# DE-110817_02.net
KiCad netlist of a schematic drawn in Altium Designer
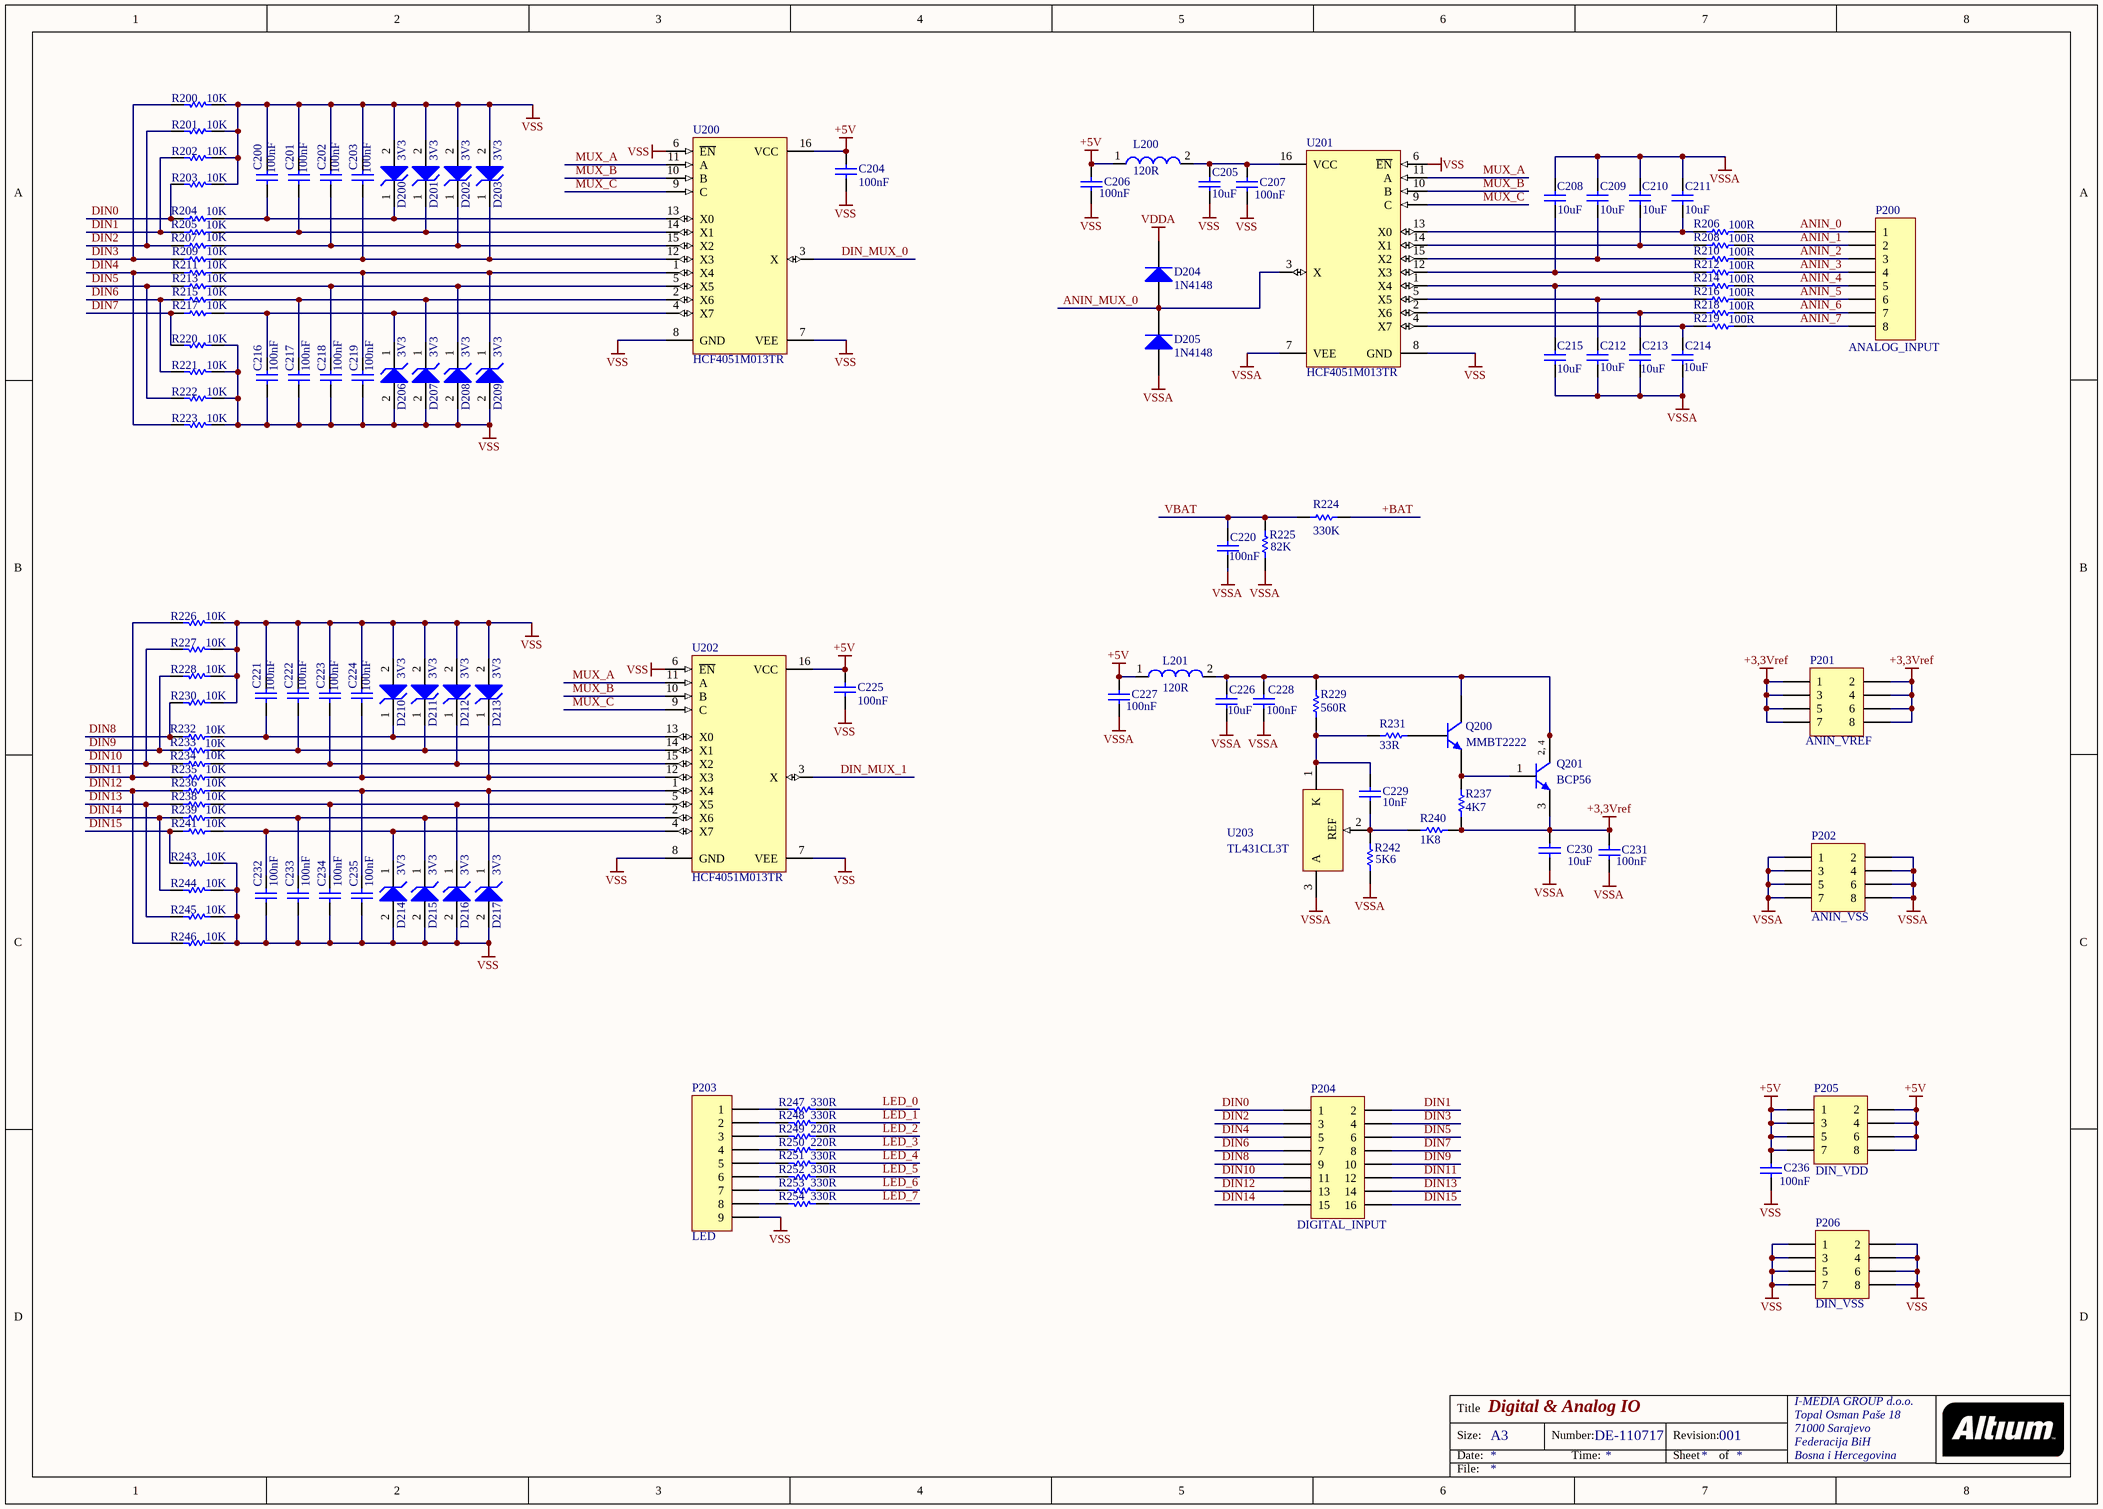
[diagram p0: DE-110817_02.SchDoc]

(export (version "E")
  (design (tool "Eeschema 10.0.6"))
  (components
    (comp (ref "C200")
      (value "100nF")
      (footprint "0603")
      (description "Ceramic Chip Capacitor - Standard")
      (libsource (lib "DE-251215") (part "C0603"))
    )
    (comp (ref "C201")
      (value "100nF")
      (footprint "0603")
      (description "Ceramic Chip Capacitor - Standard")
      (libsource (lib "DE-251215") (part "C0603"))
    )
    (comp (ref "C202")
      (value "100nF")
      (footprint "0603")
      (description "Ceramic Chip Capacitor - Standard")
      (libsource (lib "DE-251215") (part "C0603"))
    )
    (comp (ref "C203")
      (value "100nF")
      (footprint "0603")
      (description "Ceramic Chip Capacitor - Standard")
      (libsource (lib "DE-251215") (part "C0603"))
    )
    (comp (ref "C204")
      (value "100nF")
      (footprint "0603")
      (description "Ceramic Chip Capacitor - Standard")
      (libsource (lib "KEMET Chip Capacitor") (part "C0603"))
    )
    (comp (ref "C205")
      (value "10uF")
      (footprint "0805")
      (description "Ceramic Chip Capacitor - Standard")
      (libsource (lib "KEMET Chip Capacitor") (part "C0805"))
    )
    (comp (ref "C206")
      (value "100nF")
      (footprint "0603")
      (description "Ceramic Chip Capacitor - Standard")
      (libsource (lib "KEMET Chip Capacitor") (part "C0603"))
    )
    (comp (ref "C207")
      (value "100nF")
      (footprint "0603")
      (description "Ceramic Chip Capacitor - Standard")
      (libsource (lib "KEMET Chip Capacitor") (part "C0603"))
    )
    (comp (ref "C208")
      (value "10uF")
      (footprint "0805")
      (description "Ceramic Chip Capacitor - Standard")
      (libsource (lib "KEMET Chip Capacitor") (part "C0805"))
    )
    (comp (ref "C209")
      (value "10uF")
      (footprint "0805")
      (description "Ceramic Chip Capacitor - Standard")
      (libsource (lib "KEMET Chip Capacitor") (part "C0805"))
    )
    (comp (ref "C210")
      (value "10uF")
      (footprint "0805")
      (description "Ceramic Chip Capacitor - Standard")
      (libsource (lib "KEMET Chip Capacitor") (part "C0805"))
    )
    (comp (ref "C211")
      (value "10uF")
      (footprint "0805")
      (description "Ceramic Chip Capacitor - Standard")
      (libsource (lib "KEMET Chip Capacitor") (part "C0805"))
    )
    (comp (ref "C212")
      (value "10uF")
      (footprint "0805")
      (description "Ceramic Chip Capacitor - Standard")
      (libsource (lib "KEMET Chip Capacitor") (part "C0805"))
    )
    (comp (ref "C213")
      (value "10uF")
      (footprint "0805")
      (description "Ceramic Chip Capacitor - Standard")
      (libsource (lib "KEMET Chip Capacitor") (part "C0805"))
    )
    (comp (ref "C214")
      (value "10uF")
      (footprint "0805")
      (description "Ceramic Chip Capacitor - Standard")
      (libsource (lib "KEMET Chip Capacitor") (part "C0805"))
    )
    (comp (ref "C215")
      (value "10uF")
      (footprint "0805")
      (description "Ceramic Chip Capacitor - Standard")
      (libsource (lib "KEMET Chip Capacitor") (part "C0805"))
    )
    (comp (ref "C216")
      (value "100nF")
      (footprint "0603")
      (description "Ceramic Chip Capacitor - Standard")
      (libsource (lib "DE-251215") (part "C0603"))
    )
    (comp (ref "C217")
      (value "100nF")
      (footprint "0603")
      (description "Ceramic Chip Capacitor - Standard")
      (libsource (lib "DE-251215") (part "C0603"))
    )
    (comp (ref "C218")
      (value "100nF")
      (footprint "0603")
      (description "Ceramic Chip Capacitor - Standard")
      (libsource (lib "DE-251215") (part "C0603"))
    )
    (comp (ref "C219")
      (value "100nF")
      (footprint "0603")
      (description "Ceramic Chip Capacitor - Standard")
      (libsource (lib "DE-251215") (part "C0603"))
    )
    (comp (ref "C220")
      (value "100nF")
      (footprint "0603")
      (description "Ceramic Chip Capacitor - Standard")
      (libsource (lib "DE-251215") (part "C0603"))
    )
    (comp (ref "C221")
      (value "100nF")
      (footprint "0603")
      (description "Ceramic Chip Capacitor - Standard")
      (libsource (lib "DE-251215") (part "C0603"))
    )
    (comp (ref "C222")
      (value "100nF")
      (footprint "0603")
      (description "Ceramic Chip Capacitor - Standard")
      (libsource (lib "DE-251215") (part "C0603"))
    )
    (comp (ref "C223")
      (value "100nF")
      (footprint "0603")
      (description "Ceramic Chip Capacitor - Standard")
      (libsource (lib "DE-251215") (part "C0603"))
    )
    (comp (ref "C224")
      (value "100nF")
      (footprint "0603")
      (description "Ceramic Chip Capacitor - Standard")
      (libsource (lib "DE-251215") (part "C0603"))
    )
    (comp (ref "C225")
      (value "100nF")
      (footprint "0603")
      (description "Ceramic Chip Capacitor - Standard")
      (libsource (lib "KEMET Chip Capacitor") (part "C0603"))
    )
    (comp (ref "C226")
      (value "10uF")
      (footprint "0805")
      (description "Ceramic Chip Capacitor - Standard")
      (libsource (lib "KEMET Chip Capacitor") (part "C0805"))
    )
    (comp (ref "C227")
      (value "100nF")
      (footprint "0603")
      (description "Ceramic Chip Capacitor - Standard")
      (libsource (lib "KEMET Chip Capacitor") (part "C0603"))
    )
    (comp (ref "C228")
      (value "100nF")
      (footprint "0603")
      (description "Ceramic Chip Capacitor - Standard")
      (libsource (lib "KEMET Chip Capacitor") (part "C0603"))
    )
    (comp (ref "C229")
      (value "10nF")
      (footprint "0603")
      (description "Ceramic Chip Capacitor - Standard")
      (libsource (lib "KEMET Chip Capacitor") (part "C0603"))
    )
    (comp (ref "C230")
      (value "10uF")
      (footprint "0805")
      (description "Ceramic Chip Capacitor - Standard")
      (libsource (lib "KEMET Chip Capacitor") (part "C0805"))
    )
    (comp (ref "C231")
      (value "100nF")
      (footprint "0603")
      (description "Ceramic Chip Capacitor - Standard")
      (libsource (lib "KEMET Chip Capacitor") (part "C0603"))
    )
    (comp (ref "C232")
      (value "100nF")
      (footprint "0603")
      (description "Ceramic Chip Capacitor - Standard")
      (libsource (lib "DE-251215") (part "C0603"))
    )
    (comp (ref "C233")
      (value "100nF")
      (footprint "0603")
      (description "Ceramic Chip Capacitor - Standard")
      (libsource (lib "DE-251215") (part "C0603"))
    )
    (comp (ref "C234")
      (value "100nF")
      (footprint "0603")
      (description "Ceramic Chip Capacitor - Standard")
      (libsource (lib "DE-251215") (part "C0603"))
    )
    (comp (ref "C235")
      (value "100nF")
      (footprint "0603")
      (description "Ceramic Chip Capacitor - Standard")
      (libsource (lib "DE-251215") (part "C0603"))
    )
    (comp (ref "C236")
      (value "100nF")
      (footprint "0603")
      (description "Ceramic Chip Capacitor - Standard")
      (libsource (lib "KEMET Chip Capacitor") (part "C0603"))
    )
    (comp (ref "D200")
      (value "3V3")
      (footprint "ONSC-SOD-323-2-477-02_V")
      (description "Zener Voltage Regulator, 300 mW, 2-Pin SOD-323, Pb-Free, Tape and Reel")
      (fields (field (name "MANUFACTURER") "On Semiconductor") (field (name "PARTNUMBER") "MM3Z33VT1G"))
      (libsource (lib "ON Semi Zener Diodes") (part "MM3Z33VT1G"))
    )
    (comp (ref "D201")
      (value "3V3")
      (footprint "ONSC-SOD-323-2-477-02_V")
      (description "Zener Voltage Regulator, 300 mW, 2-Pin SOD-323, Pb-Free, Tape and Reel")
      (fields (field (name "MANUFACTURER") "On Semiconductor") (field (name "PARTNUMBER") "MM3Z33VT1G"))
      (libsource (lib "ON Semi Zener Diodes") (part "MM3Z33VT1G"))
    )
    (comp (ref "D202")
      (value "3V3")
      (footprint "ONSC-SOD-323-2-477-02_V")
      (description "Zener Voltage Regulator, 300 mW, 2-Pin SOD-323, Pb-Free, Tape and Reel")
      (fields (field (name "MANUFACTURER") "On Semiconductor") (field (name "PARTNUMBER") "MM3Z33VT1G"))
      (libsource (lib "ON Semi Zener Diodes") (part "MM3Z33VT1G"))
    )
    (comp (ref "D203")
      (value "3V3")
      (footprint "ONSC-SOD-323-2-477-02_V")
      (description "Zener Voltage Regulator, 300 mW, 2-Pin SOD-323, Pb-Free, Tape and Reel")
      (fields (field (name "MANUFACTURER") "On Semiconductor") (field (name "PARTNUMBER") "MM3Z33VT1G"))
      (libsource (lib "ON Semi Zener Diodes") (part "MM3Z33VT1G"))
    )
    (comp (ref "D204")
      (value "1N4148")
      (footprint "SOD323")
      (description "General-purpose Diode")
      (libsource (lib "Philips Discrete Diode - Switching") (part "BAS321"))
    )
    (comp (ref "D205")
      (value "1N4148")
      (footprint "SOD323")
      (description "General-purpose Diode")
      (libsource (lib "Philips Discrete Diode - Switching") (part "BAS321"))
    )
    (comp (ref "D206")
      (value "3V3")
      (footprint "ONSC-SOD-323-2-477-02_V")
      (description "Zener Voltage Regulator, 300 mW, 2-Pin SOD-323, Pb-Free, Tape and Reel")
      (fields (field (name "MANUFACTURER") "On Semiconductor") (field (name "PARTNUMBER") "MM3Z33VT1G"))
      (libsource (lib "ON Semi Zener Diodes") (part "MM3Z33VT1G"))
    )
    (comp (ref "D207")
      (value "3V3")
      (footprint "ONSC-SOD-323-2-477-02_V")
      (description "Zener Voltage Regulator, 300 mW, 2-Pin SOD-323, Pb-Free, Tape and Reel")
      (fields (field (name "MANUFACTURER") "On Semiconductor") (field (name "PARTNUMBER") "MM3Z33VT1G"))
      (libsource (lib "ON Semi Zener Diodes") (part "MM3Z33VT1G"))
    )
    (comp (ref "D208")
      (value "3V3")
      (footprint "ONSC-SOD-323-2-477-02_V")
      (description "Zener Voltage Regulator, 300 mW, 2-Pin SOD-323, Pb-Free, Tape and Reel")
      (fields (field (name "MANUFACTURER") "On Semiconductor") (field (name "PARTNUMBER") "MM3Z33VT1G"))
      (libsource (lib "ON Semi Zener Diodes") (part "MM3Z33VT1G"))
    )
    (comp (ref "D209")
      (value "3V3")
      (footprint "ONSC-SOD-323-2-477-02_V")
      (description "Zener Voltage Regulator, 300 mW, 2-Pin SOD-323, Pb-Free, Tape and Reel")
      (fields (field (name "MANUFACTURER") "On Semiconductor") (field (name "PARTNUMBER") "MM3Z33VT1G"))
      (libsource (lib "ON Semi Zener Diodes") (part "MM3Z33VT1G"))
    )
    (comp (ref "D210")
      (value "3V3")
      (footprint "ONSC-SOD-323-2-477-02_V")
      (description "Zener Voltage Regulator, 300 mW, 2-Pin SOD-323, Pb-Free, Tape and Reel")
      (fields (field (name "MANUFACTURER") "On Semiconductor") (field (name "PARTNUMBER") "MM3Z33VT1G"))
      (libsource (lib "ON Semi Zener Diodes") (part "MM3Z33VT1G"))
    )
    (comp (ref "D211")
      (value "3V3")
      (footprint "ONSC-SOD-323-2-477-02_V")
      (description "Zener Voltage Regulator, 300 mW, 2-Pin SOD-323, Pb-Free, Tape and Reel")
      (fields (field (name "MANUFACTURER") "On Semiconductor") (field (name "PARTNUMBER") "MM3Z33VT1G"))
      (libsource (lib "ON Semi Zener Diodes") (part "MM3Z33VT1G"))
    )
    (comp (ref "D212")
      (value "3V3")
      (footprint "ONSC-SOD-323-2-477-02_V")
      (description "Zener Voltage Regulator, 300 mW, 2-Pin SOD-323, Pb-Free, Tape and Reel")
      (fields (field (name "MANUFACTURER") "On Semiconductor") (field (name "PARTNUMBER") "MM3Z33VT1G"))
      (libsource (lib "ON Semi Zener Diodes") (part "MM3Z33VT1G"))
    )
    (comp (ref "D213")
      (value "3V3")
      (footprint "ONSC-SOD-323-2-477-02_V")
      (description "Zener Voltage Regulator, 300 mW, 2-Pin SOD-323, Pb-Free, Tape and Reel")
      (fields (field (name "MANUFACTURER") "On Semiconductor") (field (name "PARTNUMBER") "MM3Z33VT1G"))
      (libsource (lib "ON Semi Zener Diodes") (part "MM3Z33VT1G"))
    )
    (comp (ref "D214")
      (value "3V3")
      (footprint "ONSC-SOD-323-2-477-02_V")
      (description "Zener Voltage Regulator, 300 mW, 2-Pin SOD-323, Pb-Free, Tape and Reel")
      (fields (field (name "MANUFACTURER") "On Semiconductor") (field (name "PARTNUMBER") "MM3Z33VT1G"))
      (libsource (lib "ON Semi Zener Diodes") (part "MM3Z33VT1G"))
    )
    (comp (ref "D215")
      (value "3V3")
      (footprint "ONSC-SOD-323-2-477-02_V")
      (description "Zener Voltage Regulator, 300 mW, 2-Pin SOD-323, Pb-Free, Tape and Reel")
      (fields (field (name "MANUFACTURER") "On Semiconductor") (field (name "PARTNUMBER") "MM3Z33VT1G"))
      (libsource (lib "ON Semi Zener Diodes") (part "MM3Z33VT1G"))
    )
    (comp (ref "D216")
      (value "3V3")
      (footprint "ONSC-SOD-323-2-477-02_V")
      (description "Zener Voltage Regulator, 300 mW, 2-Pin SOD-323, Pb-Free, Tape and Reel")
      (fields (field (name "MANUFACTURER") "On Semiconductor") (field (name "PARTNUMBER") "MM3Z33VT1G"))
      (libsource (lib "ON Semi Zener Diodes") (part "MM3Z33VT1G"))
    )
    (comp (ref "D217")
      (value "3V3")
      (footprint "ONSC-SOD-323-2-477-02_V")
      (description "Zener Voltage Regulator, 300 mW, 2-Pin SOD-323, Pb-Free, Tape and Reel")
      (fields (field (name "MANUFACTURER") "On Semiconductor") (field (name "PARTNUMBER") "MM3Z33VT1G"))
      (libsource (lib "ON Semi Zener Diodes") (part "MM3Z33VT1G"))
    )
    (comp (ref "L200")
      (value "120R")
      (footprint "SMD-0805")
      (description "SMD EMI Suppression Ferrite Bead WE-CBF, Z = 120 Ohm")
      (fields (field (name "PARTNUMBER") "74279202"))
      (libsource (lib "WE-CBF SMD EMI Suppression Ferrite Bead") (part "74279202"))
    )
    (comp (ref "L201")
      (value "120R")
      (footprint "SMD-0805")
      (description "SMD EMI Suppression Ferrite Bead WE-CBF, Z = 120 Ohm")
      (fields (field (name "PARTNUMBER") "74279202"))
      (libsource (lib "WE-CBF SMD EMI Suppression Ferrite Bead") (part "74279202"))
    )
    (comp (ref "P200")
      (value "ANALOG_INPUT")
      (footprint "HDR1X8")
      (description "Header, 8-Pin")
      (libsource (lib "Miscellaneous Connectors") (part "Header 8"))
    )
    (comp (ref "P201")
      (value "ANIN_VREF")
      (footprint "HDR2X4")
      (description "Header, 4-Pin, Dual row")
      (libsource (lib "Miscellaneous Connectors") (part "Header 4X2"))
    )
    (comp (ref "P202")
      (value "ANIN_VSS")
      (footprint "HDR2X4")
      (description "Header, 4-Pin, Dual row")
      (libsource (lib "Miscellaneous Connectors") (part "Header 4X2"))
    )
    (comp (ref "P203")
      (value "LED")
      (footprint "HDR1X9")
      (description "Header, 9-Pin")
      (libsource (lib "Miscellaneous Connectors") (part "Header 9"))
    )
    (comp (ref "P204")
      (value "DIGITAL_INPUT")
      (footprint "HDR2X8")
      (description "Header, 8-Pin, Dual row")
      (libsource (lib "Miscellaneous Connectors") (part "Header 8X2"))
    )
    (comp (ref "P205")
      (value "DIN_VDD")
      (footprint "HDR2X4")
      (description "Header, 4-Pin, Dual row")
      (libsource (lib "Miscellaneous Connectors") (part "Header 4X2"))
    )
    (comp (ref "P206")
      (value "DIN_VSS")
      (footprint "HDR2X4")
      (description "Header, 4-Pin, Dual row")
      (libsource (lib "Miscellaneous Connectors") (part "Header 4X2"))
    )
    (comp (ref "Q200")
      (value "MMBT2222")
      (footprint "318-08")
      (description "General Purpose Transistor NPN Silicon")
      (libsource (lib "Motorola Discrete BJT") (part "MMBT2222ALT1"))
    )
    (comp (ref "Q201")
      (value "BCP56")
      (footprint "SOT223_N")
      (description "NPN Medium Power Transistor")
      (libsource (lib "Philips Discrete BJT - Medium Power") (part "BCP56"))
    )
    (comp (ref "R200") (value "10K") (footprint "ERA-0603") (libsource (lib "DE-200216_03") (part "ERAV")))
    (comp (ref "R201") (value "10K") (footprint "ERA-0603") (libsource (lib "DE-200216_03") (part "ERAV")))
    (comp (ref "R202") (value "10K") (footprint "ERA-0603") (libsource (lib "DE-200216_03") (part "ERAV")))
    (comp (ref "R203") (value "10K") (footprint "ERA-0603") (libsource (lib "DE-200216_03") (part "ERAV")))
    (comp (ref "R204") (value "10K") (footprint "ERA-0603") (libsource (lib "DE-200216_03") (part "ERAV")))
    (comp (ref "R205") (value "10K") (footprint "ERA-0603") (libsource (lib "DE-200216_03") (part "ERAV")))
    (comp (ref "R206") (value "100R") (footprint "ERA-0603") (libsource (lib "DE-200216_03") (part "ERAV")))
    (comp (ref "R207") (value "10K") (footprint "ERA-0603") (libsource (lib "DE-200216_03") (part "ERAV")))
    (comp (ref "R208") (value "100R") (footprint "ERA-0603") (libsource (lib "DE-200216_03") (part "ERAV")))
    (comp (ref "R209") (value "10K") (footprint "ERA-0603") (libsource (lib "DE-251215") (part "ERAV")))
    (comp (ref "R210") (value "100R") (footprint "ERA-0603") (libsource (lib "DE-200216_03") (part "ERAV")))
    (comp (ref "R211") (value "10K") (footprint "ERA-0603") (libsource (lib "DE-251215") (part "ERAV")))
    (comp (ref "R212") (value "100R") (footprint "ERA-0603") (libsource (lib "DE-200216_03") (part "ERAV")))
    (comp (ref "R213") (value "10K") (footprint "ERA-0603") (libsource (lib "DE-251215") (part "ERAV")))
    (comp (ref "R214") (value "100R") (footprint "ERA-0603") (libsource (lib "DE-200216_03") (part "ERAV")))
    (comp (ref "R215") (value "10K") (footprint "ERA-0603") (libsource (lib "DE-251215") (part "ERAV")))
    (comp (ref "R216") (value "100R") (footprint "ERA-0603") (libsource (lib "DE-200216_03") (part "ERAV")))
    (comp (ref "R217") (value "10K") (footprint "ERA-0603") (libsource (lib "DE-251215") (part "ERAV")))
    (comp (ref "R218") (value "100R") (footprint "ERA-0603") (libsource (lib "DE-200216_03") (part "ERAV")))
    (comp (ref "R219") (value "100R") (footprint "ERA-0603") (libsource (lib "DE-200216_03") (part "ERAV")))
    (comp (ref "R220") (value "10K") (footprint "ERA-0603") (libsource (lib "DE-200216_03") (part "ERAV")))
    (comp (ref "R221") (value "10K") (footprint "ERA-0603") (libsource (lib "DE-200216_03") (part "ERAV")))
    (comp (ref "R222") (value "10K") (footprint "ERA-0603") (libsource (lib "DE-200216_03") (part "ERAV")))
    (comp (ref "R223") (value "10K") (footprint "ERA-0603") (libsource (lib "DE-200216_03") (part "ERAV")))
    (comp (ref "R224") (value "330K") (footprint "ERA-0603") (libsource (lib "DE-200216_03") (part "ERAV")))
    (comp (ref "R225") (value "82K") (footprint "ERA-0603") (libsource (lib "DE-200216_03") (part "ERAV")))
    (comp (ref "R226") (value "10K") (footprint "ERA-0603") (libsource (lib "DE-200216_03") (part "ERAV")))
    (comp (ref "R227") (value "10K") (footprint "ERA-0603") (libsource (lib "DE-200216_03") (part "ERAV")))
    (comp (ref "R228") (value "10K") (footprint "ERA-0603") (libsource (lib "DE-200216_03") (part "ERAV")))
    (comp (ref "R229") (value "560R") (footprint "ERA-0603") (libsource (lib "DE-200216_03") (part "ERAV")))
    (comp (ref "R230") (value "10K") (footprint "ERA-0603") (libsource (lib "DE-200216_03") (part "ERAV")))
    (comp (ref "R231") (value "33R") (footprint "ERA-0603") (libsource (lib "DE-200216_03") (part "ERAV")))
    (comp (ref "R232") (value "10K") (footprint "ERA-0603") (libsource (lib "DE-200216_03") (part "ERAV")))
    (comp (ref "R233") (value "10K") (footprint "ERA-0603") (libsource (lib "DE-200216_03") (part "ERAV")))
    (comp (ref "R234") (value "10K") (footprint "ERA-0603") (libsource (lib "DE-200216_03") (part "ERAV")))
    (comp (ref "R235") (value "10K") (footprint "ERA-0603") (libsource (lib "DE-251215") (part "ERAV")))
    (comp (ref "R236") (value "10K") (footprint "ERA-0603") (libsource (lib "DE-251215") (part "ERAV")))
    (comp (ref "R237") (value "4K7") (footprint "ERA-0603") (libsource (lib "DE-200216_03") (part "ERAV")))
    (comp (ref "R238") (value "10K") (footprint "ERA-0603") (libsource (lib "DE-251215") (part "ERAV")))
    (comp (ref "R239") (value "10K") (footprint "ERA-0603") (libsource (lib "DE-251215") (part "ERAV")))
    (comp (ref "R240") (value "1K8") (footprint "ERA-0603") (libsource (lib "DE-200216_03") (part "ERAV")))
    (comp (ref "R241") (value "10K") (footprint "ERA-0603") (libsource (lib "DE-251215") (part "ERAV")))
    (comp (ref "R242") (value "5K6") (footprint "ERA-0603") (libsource (lib "DE-200216_03") (part "ERAV")))
    (comp (ref "R243") (value "10K") (footprint "ERA-0603") (libsource (lib "DE-200216_03") (part "ERAV")))
    (comp (ref "R244") (value "10K") (footprint "ERA-0603") (libsource (lib "DE-200216_03") (part "ERAV")))
    (comp (ref "R245") (value "10K") (footprint "ERA-0603") (libsource (lib "DE-200216_03") (part "ERAV")))
    (comp (ref "R246") (value "10K") (footprint "ERA-0603") (libsource (lib "DE-200216_03") (part "ERAV")))
    (comp (ref "R247") (value "330R") (footprint "ERA-0603") (libsource (lib "DE-200216_03") (part "ERAV")))
    (comp (ref "R248") (value "330R") (footprint "ERA-0603") (libsource (lib "DE-200216_03") (part "ERAV")))
    (comp (ref "R249") (value "220R") (footprint "ERA-0603") (libsource (lib "DE-200216_03") (part "ERAV")))
    (comp (ref "R250") (value "220R") (footprint "ERA-0603") (libsource (lib "DE-200216_03") (part "ERAV")))
    (comp (ref "R251") (value "330R") (footprint "ERA-0603") (libsource (lib "DE-200216_03") (part "ERAV")))
    (comp (ref "R252") (value "330R") (footprint "ERA-0603") (libsource (lib "DE-200216_03") (part "ERAV")))
    (comp (ref "R253") (value "330R") (footprint "ERA-0603") (libsource (lib "DE-200216_03") (part "ERAV")))
    (comp (ref "R254") (value "330R") (footprint "ERA-0603") (libsource (lib "DE-200216_03") (part "ERAV")))
    (comp (ref "U200")
      (value "HCF4051M013TR")
      (footprint "M16A_N")
      (description "8-Channel Analog Multiplexer/Demultiplexer")
      (libsource (lib "DE-110817") (part "CD4051BCM"))
    )
    (comp (ref "U201")
      (value "HCF4051M013TR")
      (footprint "M16A_N")
      (description "8-Channel Analog Multiplexer/Demultiplexer")
      (libsource (lib "") (part "CD4051BCM_1"))
    )
    (comp (ref "U202")
      (value "HCF4051M013TR")
      (footprint "M16A_N")
      (description "8-Channel Analog Multiplexer/Demultiplexer")
      (libsource (lib "DE-110817") (part "CD4051BCM"))
    )
    (comp (ref "U203")
      (value "TL431CL3T")
      (footprint "SOT23-3_N")
      (description "Programmable Voltage Reference, 2.5 to 36V, 3-Pin SOT23-3, Tape and Reel")
      (libsource (lib "STMicroelectronics Power Management Voltage Reference") (part "TL431CL3T"))
    )
  )
  (nets
    (net (code "1") (name "+3,3Vref") (class "Default")
      (node (ref "C230") (pin "2") (pinfunction "2_2") (pintype "passive"))
      (node (ref "C231") (pin "2") (pinfunction "2_2") (pintype "passive"))
      (node (ref "P201") (pin "1") (pinfunction "1_1") (pintype "passive"))
      (node (ref "P201") (pin "2") (pinfunction "2_2") (pintype "passive"))
      (node (ref "P201") (pin "3") (pinfunction "3_3") (pintype "passive"))
      (node (ref "P201") (pin "4") (pinfunction "4_4") (pintype "passive"))
      (node (ref "P201") (pin "5") (pinfunction "5_5") (pintype "passive"))
      (node (ref "P201") (pin "6") (pinfunction "6_6") (pintype "passive"))
      (node (ref "P201") (pin "7") (pinfunction "7_7") (pintype "passive"))
      (node (ref "P201") (pin "8") (pinfunction "8_8") (pintype "passive"))
      (node (ref "Q201") (pin "3") (pinfunction "E_3") (pintype "passive"))
      (node (ref "R237") (pin "2") (pinfunction "2_2") (pintype "passive"))
      (node (ref "R240") (pin "2") (pinfunction "2_2") (pintype "passive"))
    )
    (net (code "2") (name "+5V") (class "Default")
      (node (ref "C204") (pin "2") (pinfunction "2_2") (pintype "passive"))
      (node (ref "C206") (pin "2") (pinfunction "2_2") (pintype "passive"))
      (node (ref "C225") (pin "2") (pinfunction "2_2") (pintype "passive"))
      (node (ref "C227") (pin "2") (pinfunction "2_2") (pintype "passive"))
      (node (ref "C236") (pin "2") (pinfunction "2_2") (pintype "passive"))
      (node (ref "L200") (pin "1") (pinfunction "1_1") (pintype "passive"))
      (node (ref "L201") (pin "1") (pinfunction "1_1") (pintype "passive"))
      (node (ref "P205") (pin "1") (pinfunction "1_1") (pintype "passive"))
      (node (ref "P205") (pin "2") (pinfunction "2_2") (pintype "passive"))
      (node (ref "P205") (pin "3") (pinfunction "3_3") (pintype "passive"))
      (node (ref "P205") (pin "4") (pinfunction "4_4") (pintype "passive"))
      (node (ref "P205") (pin "5") (pinfunction "5_5") (pintype "passive"))
      (node (ref "P205") (pin "6") (pinfunction "6_6") (pintype "passive"))
      (node (ref "P205") (pin "7") (pinfunction "7_7") (pintype "passive"))
      (node (ref "P205") (pin "8") (pinfunction "8_8") (pintype "passive"))
      (node (ref "U200") (pin "16") (pinfunction "VCC_16") (pintype "power_in"))
      (node (ref "U202") (pin "16") (pinfunction "VCC_16") (pintype "power_in"))
    )
    (net (code "3") (name "/+BAT") (class "Default")
      (node (ref "R224") (pin "2") (pinfunction "2_2") (pintype "passive"))
    )
    (net (code "4") (name "/ANIN_0") (class "Default")
      (node (ref "P200") (pin "1") (pinfunction "1_1") (pintype "passive"))
      (node (ref "R206") (pin "2") (pinfunction "2_2") (pintype "passive"))
    )
    (net (code "5") (name "/ANIN_1") (class "Default")
      (node (ref "P200") (pin "2") (pinfunction "2_2") (pintype "passive"))
      (node (ref "R208") (pin "2") (pinfunction "2_2") (pintype "passive"))
    )
    (net (code "6") (name "/ANIN_2") (class "Default")
      (node (ref "P200") (pin "3") (pinfunction "3_3") (pintype "passive"))
      (node (ref "R210") (pin "2") (pinfunction "2_2") (pintype "passive"))
    )
    (net (code "7") (name "/ANIN_3") (class "Default")
      (node (ref "P200") (pin "4") (pinfunction "4_4") (pintype "passive"))
      (node (ref "R212") (pin "2") (pinfunction "2_2") (pintype "passive"))
    )
    (net (code "8") (name "/ANIN_4") (class "Default")
      (node (ref "P200") (pin "5") (pinfunction "5_5") (pintype "passive"))
      (node (ref "R214") (pin "2") (pinfunction "2_2") (pintype "passive"))
    )
    (net (code "9") (name "/ANIN_5") (class "Default")
      (node (ref "P200") (pin "6") (pinfunction "6_6") (pintype "passive"))
      (node (ref "R216") (pin "2") (pinfunction "2_2") (pintype "passive"))
    )
    (net (code "10") (name "/ANIN_6") (class "Default")
      (node (ref "P200") (pin "7") (pinfunction "7_7") (pintype "passive"))
      (node (ref "R218") (pin "2") (pinfunction "2_2") (pintype "passive"))
    )
    (net (code "11") (name "/ANIN_7") (class "Default")
      (node (ref "P200") (pin "8") (pinfunction "8_8") (pintype "passive"))
      (node (ref "R219") (pin "2") (pinfunction "2_2") (pintype "passive"))
    )
    (net (code "12") (name "/ANIN_MUX_0") (class "Default")
      (node (ref "D204") (pin "2") (pinfunction "A_2") (pintype "passive"))
      (node (ref "D205") (pin "1") (pinfunction "K_1") (pintype "passive"))
      (node (ref "U201") (pin "3") (pinfunction "X_3") (pintype "bidirectional"))
    )
    (net (code "13") (name "/DIN0") (class "Default")
      (node (ref "P204") (pin "1") (pinfunction "1_1") (pintype "passive"))
      (node (ref "R203") (pin "2") (pinfunction "2_2") (pintype "passive"))
      (node (ref "R204") (pin "1") (pinfunction "1_1") (pintype "passive"))
    )
    (net (code "14") (name "/DIN1") (class "Default")
      (node (ref "P204") (pin "2") (pinfunction "2_2") (pintype "passive"))
      (node (ref "R202") (pin "2") (pinfunction "2_2") (pintype "passive"))
      (node (ref "R205") (pin "1") (pinfunction "1_1") (pintype "passive"))
    )
    (net (code "15") (name "/DIN2") (class "Default")
      (node (ref "P204") (pin "3") (pinfunction "3_3") (pintype "passive"))
      (node (ref "R201") (pin "2") (pinfunction "2_2") (pintype "passive"))
      (node (ref "R207") (pin "1") (pinfunction "1_1") (pintype "passive"))
    )
    (net (code "16") (name "/DIN3") (class "Default")
      (node (ref "P204") (pin "4") (pinfunction "4_4") (pintype "passive"))
      (node (ref "R200") (pin "2") (pinfunction "2_2") (pintype "passive"))
      (node (ref "R209") (pin "1") (pinfunction "1_1") (pintype "passive"))
    )
    (net (code "17") (name "/DIN4") (class "Default")
      (node (ref "P204") (pin "5") (pinfunction "5_5") (pintype "passive"))
      (node (ref "R211") (pin "1") (pinfunction "1_1") (pintype "passive"))
      (node (ref "R223") (pin "2") (pinfunction "2_2") (pintype "passive"))
    )
    (net (code "18") (name "/DIN5") (class "Default")
      (node (ref "P204") (pin "6") (pinfunction "6_6") (pintype "passive"))
      (node (ref "R213") (pin "1") (pinfunction "1_1") (pintype "passive"))
      (node (ref "R222") (pin "2") (pinfunction "2_2") (pintype "passive"))
    )
    (net (code "19") (name "/DIN6") (class "Default")
      (node (ref "P204") (pin "7") (pinfunction "7_7") (pintype "passive"))
      (node (ref "R215") (pin "1") (pinfunction "1_1") (pintype "passive"))
      (node (ref "R221") (pin "2") (pinfunction "2_2") (pintype "passive"))
    )
    (net (code "20") (name "/DIN7") (class "Default")
      (node (ref "P204") (pin "8") (pinfunction "8_8") (pintype "passive"))
      (node (ref "R217") (pin "1") (pinfunction "1_1") (pintype "passive"))
      (node (ref "R220") (pin "2") (pinfunction "2_2") (pintype "passive"))
    )
    (net (code "21") (name "/DIN8") (class "Default")
      (node (ref "P204") (pin "9") (pinfunction "9_9") (pintype "passive"))
      (node (ref "R230") (pin "2") (pinfunction "2_2") (pintype "passive"))
      (node (ref "R232") (pin "1") (pinfunction "1_1") (pintype "passive"))
    )
    (net (code "22") (name "/DIN9") (class "Default")
      (node (ref "P204") (pin "10") (pinfunction "10_10") (pintype "passive"))
      (node (ref "R228") (pin "2") (pinfunction "2_2") (pintype "passive"))
      (node (ref "R233") (pin "1") (pinfunction "1_1") (pintype "passive"))
    )
    (net (code "23") (name "/DIN10") (class "Default")
      (node (ref "P204") (pin "11") (pinfunction "11_11") (pintype "passive"))
      (node (ref "R227") (pin "2") (pinfunction "2_2") (pintype "passive"))
      (node (ref "R234") (pin "1") (pinfunction "1_1") (pintype "passive"))
    )
    (net (code "24") (name "/DIN11") (class "Default")
      (node (ref "P204") (pin "12") (pinfunction "12_12") (pintype "passive"))
      (node (ref "R226") (pin "2") (pinfunction "2_2") (pintype "passive"))
      (node (ref "R235") (pin "1") (pinfunction "1_1") (pintype "passive"))
    )
    (net (code "25") (name "/DIN12") (class "Default")
      (node (ref "P204") (pin "13") (pinfunction "13_13") (pintype "passive"))
      (node (ref "R236") (pin "1") (pinfunction "1_1") (pintype "passive"))
      (node (ref "R246") (pin "2") (pinfunction "2_2") (pintype "passive"))
    )
    (net (code "26") (name "/DIN13") (class "Default")
      (node (ref "P204") (pin "14") (pinfunction "14_14") (pintype "passive"))
      (node (ref "R238") (pin "1") (pinfunction "1_1") (pintype "passive"))
      (node (ref "R245") (pin "2") (pinfunction "2_2") (pintype "passive"))
    )
    (net (code "27") (name "/DIN14") (class "Default")
      (node (ref "P204") (pin "15") (pinfunction "15_15") (pintype "passive"))
      (node (ref "R239") (pin "1") (pinfunction "1_1") (pintype "passive"))
      (node (ref "R244") (pin "2") (pinfunction "2_2") (pintype "passive"))
    )
    (net (code "28") (name "/DIN15") (class "Default")
      (node (ref "P204") (pin "16") (pinfunction "16_16") (pintype "passive"))
      (node (ref "R241") (pin "1") (pinfunction "1_1") (pintype "passive"))
      (node (ref "R243") (pin "2") (pinfunction "2_2") (pintype "passive"))
    )
    (net (code "29") (name "/DIN_MUX_0") (class "Default")
      (node (ref "U200") (pin "3") (pinfunction "X_3") (pintype "bidirectional"))
    )
    (net (code "30") (name "/DIN_MUX_1") (class "Default")
      (node (ref "U202") (pin "3") (pinfunction "X_3") (pintype "bidirectional"))
    )
    (net (code "31") (name "/LED_0") (class "Default")
      (node (ref "R247") (pin "2") (pinfunction "2_2") (pintype "passive"))
    )
    (net (code "32") (name "/LED_1") (class "Default")
      (node (ref "R248") (pin "2") (pinfunction "2_2") (pintype "passive"))
    )
    (net (code "33") (name "/LED_2") (class "Default")
      (node (ref "R249") (pin "2") (pinfunction "2_2") (pintype "passive"))
    )
    (net (code "34") (name "/LED_3") (class "Default")
      (node (ref "R250") (pin "2") (pinfunction "2_2") (pintype "passive"))
    )
    (net (code "35") (name "/LED_4") (class "Default")
      (node (ref "R251") (pin "2") (pinfunction "2_2") (pintype "passive"))
    )
    (net (code "36") (name "/LED_5") (class "Default")
      (node (ref "R252") (pin "2") (pinfunction "2_2") (pintype "passive"))
    )
    (net (code "37") (name "/LED_6") (class "Default")
      (node (ref "R253") (pin "2") (pinfunction "2_2") (pintype "passive"))
    )
    (net (code "38") (name "/LED_7") (class "Default")
      (node (ref "R254") (pin "2") (pinfunction "2_2") (pintype "passive"))
    )
    (net (code "39") (name "/MUX_A") (class "Default")
      (node (ref "U200") (pin "11") (pinfunction "A_11") (pintype "input"))
      (node (ref "U201") (pin "11") (pinfunction "A_11") (pintype "input"))
      (node (ref "U202") (pin "11") (pinfunction "A_11") (pintype "input"))
    )
    (net (code "40") (name "/MUX_B") (class "Default")
      (node (ref "U200") (pin "10") (pinfunction "B_10") (pintype "input"))
      (node (ref "U201") (pin "10") (pinfunction "B_10") (pintype "input"))
      (node (ref "U202") (pin "10") (pinfunction "B_10") (pintype "input"))
    )
    (net (code "41") (name "/MUX_C") (class "Default")
      (node (ref "U200") (pin "9") (pinfunction "C_9") (pintype "input"))
      (node (ref "U201") (pin "9") (pinfunction "C_9") (pintype "input"))
      (node (ref "U202") (pin "9") (pinfunction "C_9") (pintype "input"))
    )
    (net (code "42") (name "/VBAT") (class "Default")
      (node (ref "C220") (pin "2") (pinfunction "2_2") (pintype "passive"))
      (node (ref "R224") (pin "1") (pinfunction "1_1") (pintype "passive"))
      (node (ref "R225") (pin "2") (pinfunction "2_2") (pintype "passive"))
    )
    (net (code "43") (name "Net-(D200-K)") (class "Default")
      (node (ref "C200") (pin "2") (pinfunction "2_2") (pintype "passive"))
      (node (ref "D200") (pin "1") (pinfunction "K_1") (pintype "passive"))
      (node (ref "R204") (pin "2") (pinfunction "2_2") (pintype "passive"))
      (node (ref "U200") (pin "13") (pinfunction "X0_13") (pintype "bidirectional"))
    )
    (net (code "44") (name "Net-(D201-K)") (class "Default")
      (node (ref "C201") (pin "2") (pinfunction "2_2") (pintype "passive"))
      (node (ref "D201") (pin "1") (pinfunction "K_1") (pintype "passive"))
      (node (ref "R205") (pin "2") (pinfunction "2_2") (pintype "passive"))
      (node (ref "U200") (pin "14") (pinfunction "X1_14") (pintype "bidirectional"))
    )
    (net (code "45") (name "Net-(D202-K)") (class "Default")
      (node (ref "C202") (pin "2") (pinfunction "2_2") (pintype "passive"))
      (node (ref "D202") (pin "1") (pinfunction "K_1") (pintype "passive"))
      (node (ref "R207") (pin "2") (pinfunction "2_2") (pintype "passive"))
      (node (ref "U200") (pin "15") (pinfunction "X2_15") (pintype "bidirectional"))
    )
    (net (code "46") (name "Net-(D203-K)") (class "Default")
      (node (ref "C203") (pin "2") (pinfunction "2_2") (pintype "passive"))
      (node (ref "D203") (pin "1") (pinfunction "K_1") (pintype "passive"))
      (node (ref "R209") (pin "2") (pinfunction "2_2") (pintype "passive"))
      (node (ref "U200") (pin "12") (pinfunction "X3_12") (pintype "bidirectional"))
    )
    (net (code "47") (name "Net-(D206-K)") (class "Default")
      (node (ref "C216") (pin "2") (pinfunction "2_2") (pintype "passive"))
      (node (ref "D206") (pin "1") (pinfunction "K_1") (pintype "passive"))
      (node (ref "R217") (pin "2") (pinfunction "2_2") (pintype "passive"))
      (node (ref "U200") (pin "4") (pinfunction "X7_4") (pintype "bidirectional"))
    )
    (net (code "48") (name "Net-(D207-K)") (class "Default")
      (node (ref "C217") (pin "2") (pinfunction "2_2") (pintype "passive"))
      (node (ref "D207") (pin "1") (pinfunction "K_1") (pintype "passive"))
      (node (ref "R215") (pin "2") (pinfunction "2_2") (pintype "passive"))
      (node (ref "U200") (pin "2") (pinfunction "X6_2") (pintype "bidirectional"))
    )
    (net (code "49") (name "Net-(D208-K)") (class "Default")
      (node (ref "C218") (pin "2") (pinfunction "2_2") (pintype "passive"))
      (node (ref "D208") (pin "1") (pinfunction "K_1") (pintype "passive"))
      (node (ref "R213") (pin "2") (pinfunction "2_2") (pintype "passive"))
      (node (ref "U200") (pin "5") (pinfunction "X5_5") (pintype "bidirectional"))
    )
    (net (code "50") (name "Net-(D209-K)") (class "Default")
      (node (ref "C219") (pin "2") (pinfunction "2_2") (pintype "passive"))
      (node (ref "D209") (pin "1") (pinfunction "K_1") (pintype "passive"))
      (node (ref "R211") (pin "2") (pinfunction "2_2") (pintype "passive"))
      (node (ref "U200") (pin "1") (pinfunction "X4_1") (pintype "bidirectional"))
    )
    (net (code "51") (name "Net-(D210-K)") (class "Default")
      (node (ref "C221") (pin "2") (pinfunction "2_2") (pintype "passive"))
      (node (ref "D210") (pin "1") (pinfunction "K_1") (pintype "passive"))
      (node (ref "R232") (pin "2") (pinfunction "2_2") (pintype "passive"))
      (node (ref "U202") (pin "13") (pinfunction "X0_13") (pintype "bidirectional"))
    )
    (net (code "52") (name "Net-(D211-K)") (class "Default")
      (node (ref "C222") (pin "2") (pinfunction "2_2") (pintype "passive"))
      (node (ref "D211") (pin "1") (pinfunction "K_1") (pintype "passive"))
      (node (ref "R233") (pin "2") (pinfunction "2_2") (pintype "passive"))
      (node (ref "U202") (pin "14") (pinfunction "X1_14") (pintype "bidirectional"))
    )
    (net (code "53") (name "Net-(D212-K)") (class "Default")
      (node (ref "C223") (pin "2") (pinfunction "2_2") (pintype "passive"))
      (node (ref "D212") (pin "1") (pinfunction "K_1") (pintype "passive"))
      (node (ref "R234") (pin "2") (pinfunction "2_2") (pintype "passive"))
      (node (ref "U202") (pin "15") (pinfunction "X2_15") (pintype "bidirectional"))
    )
    (net (code "54") (name "Net-(D213-K)") (class "Default")
      (node (ref "C224") (pin "2") (pinfunction "2_2") (pintype "passive"))
      (node (ref "D213") (pin "1") (pinfunction "K_1") (pintype "passive"))
      (node (ref "R235") (pin "2") (pinfunction "2_2") (pintype "passive"))
      (node (ref "U202") (pin "12") (pinfunction "X3_12") (pintype "bidirectional"))
    )
    (net (code "55") (name "Net-(D214-K)") (class "Default")
      (node (ref "C232") (pin "2") (pinfunction "2_2") (pintype "passive"))
      (node (ref "D214") (pin "1") (pinfunction "K_1") (pintype "passive"))
      (node (ref "R241") (pin "2") (pinfunction "2_2") (pintype "passive"))
      (node (ref "U202") (pin "4") (pinfunction "X7_4") (pintype "bidirectional"))
    )
    (net (code "56") (name "Net-(D215-K)") (class "Default")
      (node (ref "C233") (pin "2") (pinfunction "2_2") (pintype "passive"))
      (node (ref "D215") (pin "1") (pinfunction "K_1") (pintype "passive"))
      (node (ref "R239") (pin "2") (pinfunction "2_2") (pintype "passive"))
      (node (ref "U202") (pin "2") (pinfunction "X6_2") (pintype "bidirectional"))
    )
    (net (code "57") (name "Net-(D216-K)") (class "Default")
      (node (ref "C234") (pin "2") (pinfunction "2_2") (pintype "passive"))
      (node (ref "D216") (pin "1") (pinfunction "K_1") (pintype "passive"))
      (node (ref "R238") (pin "2") (pinfunction "2_2") (pintype "passive"))
      (node (ref "U202") (pin "5") (pinfunction "X5_5") (pintype "bidirectional"))
    )
    (net (code "58") (name "Net-(D217-K)") (class "Default")
      (node (ref "C235") (pin "2") (pinfunction "2_2") (pintype "passive"))
      (node (ref "D217") (pin "1") (pinfunction "K_1") (pintype "passive"))
      (node (ref "R236") (pin "2") (pinfunction "2_2") (pintype "passive"))
      (node (ref "U202") (pin "1") (pinfunction "X4_1") (pintype "bidirectional"))
    )
    (net (code "59") (name "Net-(P203-Pad1)") (class "Default")
      (node (ref "P203") (pin "1") (pinfunction "1_1") (pintype "passive"))
      (node (ref "R247") (pin "1") (pinfunction "1_1") (pintype "passive"))
    )
    (net (code "60") (name "Net-(P203-Pad2)") (class "Default")
      (node (ref "P203") (pin "2") (pinfunction "2_2") (pintype "passive"))
      (node (ref "R248") (pin "1") (pinfunction "1_1") (pintype "passive"))
    )
    (net (code "61") (name "Net-(P203-Pad3)") (class "Default")
      (node (ref "P203") (pin "3") (pinfunction "3_3") (pintype "passive"))
      (node (ref "R249") (pin "1") (pinfunction "1_1") (pintype "passive"))
    )
    (net (code "62") (name "Net-(P203-Pad4)") (class "Default")
      (node (ref "P203") (pin "4") (pinfunction "4_4") (pintype "passive"))
      (node (ref "R250") (pin "1") (pinfunction "1_1") (pintype "passive"))
    )
    (net (code "63") (name "Net-(P203-Pad5)") (class "Default")
      (node (ref "P203") (pin "5") (pinfunction "5_5") (pintype "passive"))
      (node (ref "R251") (pin "1") (pinfunction "1_1") (pintype "passive"))
    )
    (net (code "64") (name "Net-(P203-Pad6)") (class "Default")
      (node (ref "P203") (pin "6") (pinfunction "6_6") (pintype "passive"))
      (node (ref "R252") (pin "1") (pinfunction "1_1") (pintype "passive"))
    )
    (net (code "65") (name "Net-(P203-Pad7)") (class "Default")
      (node (ref "P203") (pin "7") (pinfunction "7_7") (pintype "passive"))
      (node (ref "R253") (pin "1") (pinfunction "1_1") (pintype "passive"))
    )
    (net (code "66") (name "Net-(P203-Pad8)") (class "Default")
      (node (ref "P203") (pin "8") (pinfunction "8_8") (pintype "passive"))
      (node (ref "R254") (pin "1") (pinfunction "1_1") (pintype "passive"))
    )
    (net (code "67") (name "Net-(Q200-B)") (class "Default")
      (node (ref "Q200") (pin "1") (pinfunction "B_1") (pintype "passive"))
      (node (ref "R231") (pin "1") (pinfunction "1_1") (pintype "passive"))
    )
    (net (code "68") (name "Net-(Q200-C)") (class "Default")
      (node (ref "C226") (pin "2") (pinfunction "2_2") (pintype "passive"))
      (node (ref "C228") (pin "2") (pinfunction "2_2") (pintype "passive"))
      (node (ref "L201") (pin "2") (pinfunction "2_2") (pintype "passive"))
      (node (ref "Q200") (pin "3") (pinfunction "C_3") (pintype "passive"))
      (node (ref "Q201") (pin "2") (pinfunction "C_2") (pintype "passive"))
      (node (ref "Q201") (pin "4") (pinfunction "C_4") (pintype "passive"))
      (node (ref "R229") (pin "2") (pinfunction "2_2") (pintype "passive"))
    )
    (net (code "69") (name "Net-(Q200-E)") (class "Default")
      (node (ref "Q200") (pin "2") (pinfunction "E_2") (pintype "passive"))
      (node (ref "Q201") (pin "1") (pinfunction "B_1") (pintype "passive"))
      (node (ref "R237") (pin "1") (pinfunction "1_1") (pintype "passive"))
    )
    (net (code "70") (name "Net-(U201-VCC)") (class "Default")
      (node (ref "C205") (pin "2") (pinfunction "2_2") (pintype "passive"))
      (node (ref "C207") (pin "2") (pinfunction "2_2") (pintype "passive"))
      (node (ref "L200") (pin "2") (pinfunction "2_2") (pintype "passive"))
      (node (ref "U201") (pin "16") (pinfunction "VCC_16") (pintype "power_in"))
    )
    (net (code "71") (name "Net-(U201-X0)") (class "Default")
      (node (ref "C211") (pin "2") (pinfunction "2_2") (pintype "passive"))
      (node (ref "R206") (pin "1") (pinfunction "1_1") (pintype "passive"))
      (node (ref "U201") (pin "13") (pinfunction "X0_13") (pintype "bidirectional"))
    )
    (net (code "72") (name "Net-(U201-X1)") (class "Default")
      (node (ref "C210") (pin "2") (pinfunction "2_2") (pintype "passive"))
      (node (ref "R208") (pin "1") (pinfunction "1_1") (pintype "passive"))
      (node (ref "U201") (pin "14") (pinfunction "X1_14") (pintype "bidirectional"))
    )
    (net (code "73") (name "Net-(U201-X2)") (class "Default")
      (node (ref "C209") (pin "2") (pinfunction "2_2") (pintype "passive"))
      (node (ref "R210") (pin "1") (pinfunction "1_1") (pintype "passive"))
      (node (ref "U201") (pin "15") (pinfunction "X2_15") (pintype "bidirectional"))
    )
    (net (code "74") (name "Net-(U201-X3)") (class "Default")
      (node (ref "C208") (pin "2") (pinfunction "2_2") (pintype "passive"))
      (node (ref "R212") (pin "1") (pinfunction "1_1") (pintype "passive"))
      (node (ref "U201") (pin "12") (pinfunction "X3_12") (pintype "bidirectional"))
    )
    (net (code "75") (name "Net-(U201-X4)") (class "Default")
      (node (ref "C215") (pin "2") (pinfunction "2_2") (pintype "passive"))
      (node (ref "R214") (pin "1") (pinfunction "1_1") (pintype "passive"))
      (node (ref "U201") (pin "1") (pinfunction "X4_1") (pintype "bidirectional"))
    )
    (net (code "76") (name "Net-(U201-X5)") (class "Default")
      (node (ref "C212") (pin "2") (pinfunction "2_2") (pintype "passive"))
      (node (ref "R216") (pin "1") (pinfunction "1_1") (pintype "passive"))
      (node (ref "U201") (pin "5") (pinfunction "X5_5") (pintype "bidirectional"))
    )
    (net (code "77") (name "Net-(U201-X6)") (class "Default")
      (node (ref "C213") (pin "2") (pinfunction "2_2") (pintype "passive"))
      (node (ref "R218") (pin "1") (pinfunction "1_1") (pintype "passive"))
      (node (ref "U201") (pin "2") (pinfunction "X6_2") (pintype "bidirectional"))
    )
    (net (code "78") (name "Net-(U201-X7)") (class "Default")
      (node (ref "C214") (pin "2") (pinfunction "2_2") (pintype "passive"))
      (node (ref "R219") (pin "1") (pinfunction "1_1") (pintype "passive"))
      (node (ref "U201") (pin "4") (pinfunction "X7_4") (pintype "bidirectional"))
    )
    (net (code "79") (name "Net-(U203-K)") (class "Default")
      (node (ref "C229") (pin "1") (pinfunction "1_1") (pintype "passive"))
      (node (ref "R229") (pin "1") (pinfunction "1_1") (pintype "passive"))
      (node (ref "R231") (pin "2") (pinfunction "2_2") (pintype "passive"))
      (node (ref "U203") (pin "1") (pinfunction "K_1") (pintype "passive"))
    )
    (net (code "80") (name "Net-(U203-REF)") (class "Default")
      (node (ref "C229") (pin "2") (pinfunction "2_2") (pintype "passive"))
      (node (ref "R240") (pin "1") (pinfunction "1_1") (pintype "passive"))
      (node (ref "R242") (pin "1") (pinfunction "1_1") (pintype "passive"))
      (node (ref "U203") (pin "2") (pinfunction "REF_2") (pintype "input"))
    )
    (net (code "81") (name "VDDA") (class "Default")
      (node (ref "D204") (pin "1") (pinfunction "K_1") (pintype "passive"))
    )
    (net (code "82") (name "VSS") (class "Default")
      (node (ref "C200") (pin "1") (pinfunction "1_1") (pintype "passive"))
      (node (ref "C201") (pin "1") (pinfunction "1_1") (pintype "passive"))
      (node (ref "C202") (pin "1") (pinfunction "1_1") (pintype "passive"))
      (node (ref "C203") (pin "1") (pinfunction "1_1") (pintype "passive"))
      (node (ref "C204") (pin "1") (pinfunction "1_1") (pintype "passive"))
      (node (ref "C205") (pin "1") (pinfunction "1_1") (pintype "passive"))
      (node (ref "C206") (pin "1") (pinfunction "1_1") (pintype "passive"))
      (node (ref "C207") (pin "1") (pinfunction "1_1") (pintype "passive"))
      (node (ref "C216") (pin "1") (pinfunction "1_1") (pintype "passive"))
      (node (ref "C217") (pin "1") (pinfunction "1_1") (pintype "passive"))
      (node (ref "C218") (pin "1") (pinfunction "1_1") (pintype "passive"))
      (node (ref "C219") (pin "1") (pinfunction "1_1") (pintype "passive"))
      (node (ref "C221") (pin "1") (pinfunction "1_1") (pintype "passive"))
      (node (ref "C222") (pin "1") (pinfunction "1_1") (pintype "passive"))
      (node (ref "C223") (pin "1") (pinfunction "1_1") (pintype "passive"))
      (node (ref "C224") (pin "1") (pinfunction "1_1") (pintype "passive"))
      (node (ref "C225") (pin "1") (pinfunction "1_1") (pintype "passive"))
      (node (ref "C232") (pin "1") (pinfunction "1_1") (pintype "passive"))
      (node (ref "C233") (pin "1") (pinfunction "1_1") (pintype "passive"))
      (node (ref "C234") (pin "1") (pinfunction "1_1") (pintype "passive"))
      (node (ref "C235") (pin "1") (pinfunction "1_1") (pintype "passive"))
      (node (ref "C236") (pin "1") (pinfunction "1_1") (pintype "passive"))
      (node (ref "D200") (pin "2") (pinfunction "A_2") (pintype "passive"))
      (node (ref "D201") (pin "2") (pinfunction "A_2") (pintype "passive"))
      (node (ref "D202") (pin "2") (pinfunction "A_2") (pintype "passive"))
      (node (ref "D203") (pin "2") (pinfunction "A_2") (pintype "passive"))
      (node (ref "D206") (pin "2") (pinfunction "A_2") (pintype "passive"))
      (node (ref "D207") (pin "2") (pinfunction "A_2") (pintype "passive"))
      (node (ref "D208") (pin "2") (pinfunction "A_2") (pintype "passive"))
      (node (ref "D209") (pin "2") (pinfunction "A_2") (pintype "passive"))
      (node (ref "D210") (pin "2") (pinfunction "A_2") (pintype "passive"))
      (node (ref "D211") (pin "2") (pinfunction "A_2") (pintype "passive"))
      (node (ref "D212") (pin "2") (pinfunction "A_2") (pintype "passive"))
      (node (ref "D213") (pin "2") (pinfunction "A_2") (pintype "passive"))
      (node (ref "D214") (pin "2") (pinfunction "A_2") (pintype "passive"))
      (node (ref "D215") (pin "2") (pinfunction "A_2") (pintype "passive"))
      (node (ref "D216") (pin "2") (pinfunction "A_2") (pintype "passive"))
      (node (ref "D217") (pin "2") (pinfunction "A_2") (pintype "passive"))
      (node (ref "P203") (pin "9") (pinfunction "9_9") (pintype "passive"))
      (node (ref "P206") (pin "1") (pinfunction "1_1") (pintype "passive"))
      (node (ref "P206") (pin "2") (pinfunction "2_2") (pintype "passive"))
      (node (ref "P206") (pin "3") (pinfunction "3_3") (pintype "passive"))
      (node (ref "P206") (pin "4") (pinfunction "4_4") (pintype "passive"))
      (node (ref "P206") (pin "5") (pinfunction "5_5") (pintype "passive"))
      (node (ref "P206") (pin "6") (pinfunction "6_6") (pintype "passive"))
      (node (ref "P206") (pin "7") (pinfunction "7_7") (pintype "passive"))
      (node (ref "P206") (pin "8") (pinfunction "8_8") (pintype "passive"))
      (node (ref "R200") (pin "1") (pinfunction "1_1") (pintype "passive"))
      (node (ref "R201") (pin "1") (pinfunction "1_1") (pintype "passive"))
      (node (ref "R202") (pin "1") (pinfunction "1_1") (pintype "passive"))
      (node (ref "R203") (pin "1") (pinfunction "1_1") (pintype "passive"))
      (node (ref "R220") (pin "1") (pinfunction "1_1") (pintype "passive"))
      (node (ref "R221") (pin "1") (pinfunction "1_1") (pintype "passive"))
      (node (ref "R222") (pin "1") (pinfunction "1_1") (pintype "passive"))
      (node (ref "R223") (pin "1") (pinfunction "1_1") (pintype "passive"))
      (node (ref "R226") (pin "1") (pinfunction "1_1") (pintype "passive"))
      (node (ref "R227") (pin "1") (pinfunction "1_1") (pintype "passive"))
      (node (ref "R228") (pin "1") (pinfunction "1_1") (pintype "passive"))
      (node (ref "R230") (pin "1") (pinfunction "1_1") (pintype "passive"))
      (node (ref "R243") (pin "1") (pinfunction "1_1") (pintype "passive"))
      (node (ref "R244") (pin "1") (pinfunction "1_1") (pintype "passive"))
      (node (ref "R245") (pin "1") (pinfunction "1_1") (pintype "passive"))
      (node (ref "R246") (pin "1") (pinfunction "1_1") (pintype "passive"))
      (node (ref "U200") (pin "6") (pinfunction "~{EN}_6") (pintype "input"))
      (node (ref "U200") (pin "7") (pinfunction "VEE_7") (pintype "power_in"))
      (node (ref "U200") (pin "8") (pinfunction "GND_8") (pintype "power_in"))
      (node (ref "U201") (pin "6") (pinfunction "~{EN}_6") (pintype "input"))
      (node (ref "U201") (pin "8") (pinfunction "GND_8") (pintype "power_in"))
      (node (ref "U202") (pin "6") (pinfunction "~{EN}_6") (pintype "input"))
      (node (ref "U202") (pin "7") (pinfunction "VEE_7") (pintype "power_in"))
      (node (ref "U202") (pin "8") (pinfunction "GND_8") (pintype "power_in"))
    )
    (net (code "83") (name "VSSA") (class "Default")
      (node (ref "C208") (pin "1") (pinfunction "1_1") (pintype "passive"))
      (node (ref "C209") (pin "1") (pinfunction "1_1") (pintype "passive"))
      (node (ref "C210") (pin "1") (pinfunction "1_1") (pintype "passive"))
      (node (ref "C211") (pin "1") (pinfunction "1_1") (pintype "passive"))
      (node (ref "C212") (pin "1") (pinfunction "1_1") (pintype "passive"))
      (node (ref "C213") (pin "1") (pinfunction "1_1") (pintype "passive"))
      (node (ref "C214") (pin "1") (pinfunction "1_1") (pintype "passive"))
      (node (ref "C215") (pin "1") (pinfunction "1_1") (pintype "passive"))
      (node (ref "C220") (pin "1") (pinfunction "1_1") (pintype "passive"))
      (node (ref "C226") (pin "1") (pinfunction "1_1") (pintype "passive"))
      (node (ref "C227") (pin "1") (pinfunction "1_1") (pintype "passive"))
      (node (ref "C228") (pin "1") (pinfunction "1_1") (pintype "passive"))
      (node (ref "C230") (pin "1") (pinfunction "1_1") (pintype "passive"))
      (node (ref "C231") (pin "1") (pinfunction "1_1") (pintype "passive"))
      (node (ref "D205") (pin "2") (pinfunction "A_2") (pintype "passive"))
      (node (ref "P202") (pin "1") (pinfunction "1_1") (pintype "passive"))
      (node (ref "P202") (pin "2") (pinfunction "2_2") (pintype "passive"))
      (node (ref "P202") (pin "3") (pinfunction "3_3") (pintype "passive"))
      (node (ref "P202") (pin "4") (pinfunction "4_4") (pintype "passive"))
      (node (ref "P202") (pin "5") (pinfunction "5_5") (pintype "passive"))
      (node (ref "P202") (pin "6") (pinfunction "6_6") (pintype "passive"))
      (node (ref "P202") (pin "7") (pinfunction "7_7") (pintype "passive"))
      (node (ref "P202") (pin "8") (pinfunction "8_8") (pintype "passive"))
      (node (ref "R225") (pin "1") (pinfunction "1_1") (pintype "passive"))
      (node (ref "R242") (pin "2") (pinfunction "2_2") (pintype "passive"))
      (node (ref "U201") (pin "7") (pinfunction "VEE_7") (pintype "power_in"))
      (node (ref "U203") (pin "3") (pinfunction "A_3") (pintype "passive"))
    )
  )
)
